# Main.net
KiCad netlist of a schematic drawn in Altium Designer
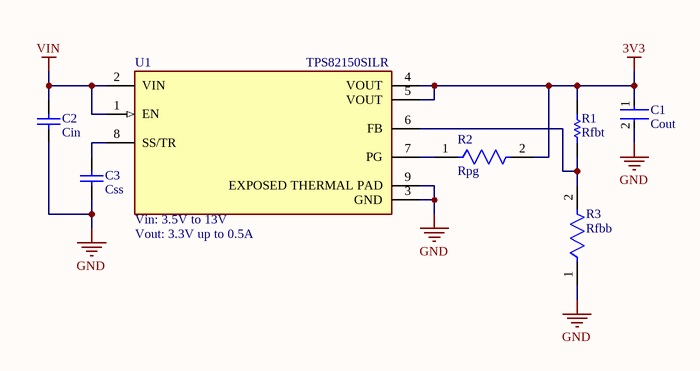
[diagram p0: Main.SchDoc]

(export (version "E")
  (design (tool "Eeschema 10.0.6"))
  (components
    (comp (ref "C1")
      (value "Cout")
      (footprint "FP-GRM21B-0_15-MFG")
      (description "Chip Multilayer Ceramic Capacitors for General Purpose, 0805, 22uF, X5R, 15%, 20%, 6.3V")
      (fields (field (name "VOLTAGE") "6.3V") (field (name "TOLERANCE") "20%"))
      (libsource (lib "Altium Content Vault") (part "b4654b650e69147ec39a6b967a45e02"))
    )
    (comp (ref "C2")
      (value "Cin")
      (footprint "CAPC3216X180X55LL20T25")
      (description "Chip Capacitor, 10 uF, +/- 10%, 16 V, -55 to 125 degC, 1206 (3216 Metric), RoHS, Tape and Reel")
      (fields (field (name "MANUFACTURER") "Murata") (field (name "TOLERANCE") "±10%"))
      (libsource (lib "Altium Content Vault") (part "CAP-NP-2"))
    )
    (comp (ref "C3")
      (value "Css")
      (footprint "CAPC1005X55X25NL05T10")
      (fields (field (name "PART NUMBER") "GRM1555C1E431JA01D") (field (name "MANUFACTURER") "Murata"))
      (libsource (lib "Altium Content Vault") (part "CAP"))
    )
    (comp (ref "R1")
      (value "Rfbt")
      (footprint "RESC1005X40X25LL05T05")
      (description "309k Ohm Chip Resistor, 0 Ohm, 0.1 W, -55 to 155 degC, 0402 (1005 Metric), RoHS, Tape and Reel")
      (fields (field (name "MANUFACTURER") "Panasonic") (field (name "TOLERANCE") "5%"))
      (libsource (lib "Altium Content Vault") (part "RES-2"))
    )
    (comp (ref "R2")
      (value "Rpg")
      (footprint "FP-CRCW0402-e3-IPC_C")
      (description "RES Thick Film, 100kΩ, 1%, 0.063W, 100ppm/°C, 0402")
      (fields (field (name "TOLERANCE") "1%"))
      (libsource (lib "Altium Content Vault") (part "1029c3af85768c4190bb7ad29bc67b5"))
    )
    (comp (ref "R3")
      (value "Rfbb")
      (footprint "FP-CRCW0402-e3-IPC_C")
      (description "RES Thick Film, 100kΩ, 1%, 0.063W, 100ppm/°C, 0402")
      (fields (field (name "TOLERANCE") "1%"))
      (libsource (lib "Altium Content Vault") (part "1029c3af85768c4190bb7ad29bc67b5"))
    )
    (comp (ref "U1")
      (value "TPS82150SILR")
      (footprint "FP-SIL0008D-MFG")
      (description "Non-Isolated PoL Module DC DC Converter 1 Output 0.9 ~ 6V    1A 3V - 17V Input")
      (fields (field (name "MANUFACTURER") "Texas Instruments"))
      (libsource (lib "Altium Content Vault") (part "1baac67358bb9c5e92d342756521ad3"))
    )
  )
  (nets
    (net (code "1") (name "3V3") (class "Default")
      (node (ref "C1") (pin "1") (pinfunction "1_1") (pintype "passive"))
      (node (ref "R1") (pin "2") (pinfunction "2_2") (pintype "passive"))
      (node (ref "R2") (pin "2") (pinfunction "2_2") (pintype "passive"))
      (node (ref "U1") (pin "4") (pinfunction "VOUT_4") (pintype "passive"))
      (node (ref "U1") (pin "5") (pinfunction "VOUT_5") (pintype "passive"))
    )
    (net (code "2") (name "GND") (class "Default")
      (node (ref "C1") (pin "2") (pinfunction "2_2") (pintype "passive"))
      (node (ref "C2") (pin "1") (pinfunction "1_1") (pintype "passive"))
      (node (ref "C3") (pin "1") (pinfunction "1_1") (pintype "passive"))
      (node (ref "R3") (pin "1") (pinfunction "1_1") (pintype "passive"))
      (node (ref "U1") (pin "3") (pinfunction "GND_3") (pintype "power_in"))
      (node (ref "U1") (pin "9") (pinfunction "EXPOSED_THERMAL_PAD_9") (pintype "power_in"))
    )
    (net (code "3") (name "Net-(U1-FB)") (class "Default")
      (node (ref "R1") (pin "1") (pinfunction "1_1") (pintype "passive"))
      (node (ref "R3") (pin "2") (pinfunction "2_2") (pintype "passive"))
      (node (ref "U1") (pin "6") (pinfunction "FB_6") (pintype "passive"))
    )
    (net (code "4") (name "Net-(U1-PG)") (class "Default")
      (node (ref "R2") (pin "1") (pinfunction "1_1") (pintype "passive"))
      (node (ref "U1") (pin "7") (pinfunction "PG_7") (pintype "open_collector"))
    )
    (net (code "5") (name "Net-(U1-SS{slash}TR)") (class "Default")
      (node (ref "C3") (pin "2") (pinfunction "2_2") (pintype "passive"))
      (node (ref "U1") (pin "8") (pinfunction "SS/TR_8") (pintype "passive"))
    )
    (net (code "6") (name "VIN") (class "Default")
      (node (ref "C2") (pin "2") (pinfunction "2_2") (pintype "passive"))
      (node (ref "U1") (pin "1") (pinfunction "EN_1") (pintype "input"))
      (node (ref "U1") (pin "2") (pinfunction "VIN_2") (pintype "power_in"))
    )
  )
)
